# Medida_tension.net
KiCad netlist of a schematic drawn in Altium Designer
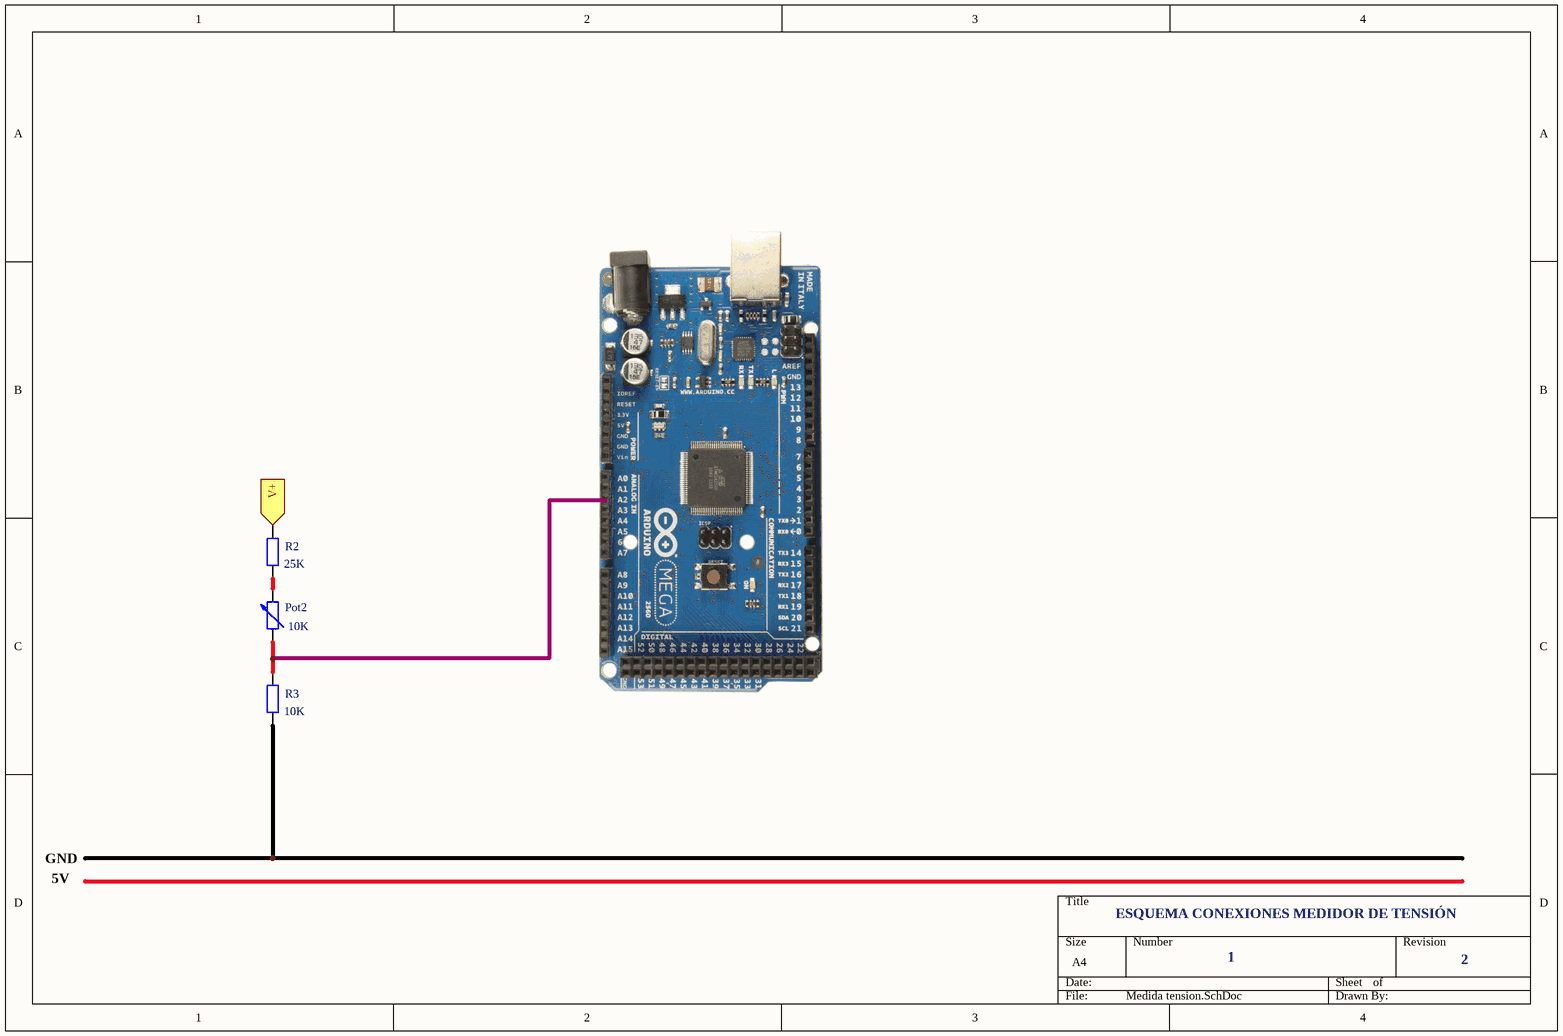
[diagram p0: Medida tension.SchDoc]

(export (version "E")
  (design (tool "Eeschema 10.0.6"))
  (components
    (comp (ref "Pot2")
      (value "10K")
      (footprint "AXIAL-0.6")
      (description "Variable Resistor")
      (fields (field (name "Comment") "Res Adj2") (field (name "PUBLISHER") "Altium Limited"))
      (libsource (lib "Miscellaneous Devices") (part "Res Adj2"))
    )
    (comp (ref "R2")
      (value "25K")
      (footprint "AXIAL-0.4")
      (description "Resistor")
      (fields (field (name "Comment") "Res2") (field (name "PUBLISHER") "Altium Limited"))
      (libsource (lib "Miscellaneous Devices") (part "Res2"))
    )
    (comp (ref "R3")
      (value "10K")
      (footprint "AXIAL-0.4")
      (description "Resistor")
      (fields (field (name "Comment") "Res2") (field (name "PUBLISHER") "Altium Limited"))
      (libsource (lib "Miscellaneous Devices") (part "Res2"))
    )
  )
  (nets
    (net (code "1") (name "/V+") (class "Default")
      (node (ref "R2") (pin "2") (pinfunction "2_2") (pintype "passive"))
    )
    (net (code "2") (name "Net-(Pot2-Pad1)") (class "Default")
      (node (ref "Pot2") (pin "1") (pinfunction "1_1") (pintype "passive"))
      (node (ref "R3") (pin "2") (pinfunction "2_2") (pintype "passive"))
    )
    (net (code "3") (name "Net-(Pot2-Pad2)") (class "Default")
      (node (ref "Pot2") (pin "2") (pinfunction "2_2") (pintype "passive"))
      (node (ref "R2") (pin "1") (pinfunction "1_1") (pintype "passive"))
    )
    (net (code "4") (name "unconnected-(R3-Pad1)") (class "Default")
      (node (ref "R3") (pin "1") (pinfunction "1_1") (pintype "passive"))
    )
  )
)
